# caphumidsens2_rev1_rc2.net
KiCad netlist of a schematic drawn in EAGLE
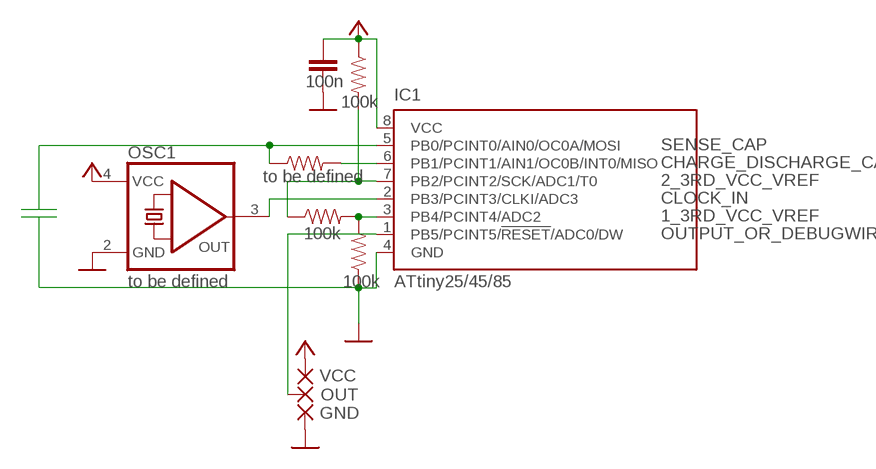
[diagram p0: schematic, sheet 1]

(export (version "E")
  (design (tool "Eeschema 10.0.6"))
  (components
    (comp (ref "C1")
      (value "100n")
      (footprint "eagle-import:0805")
      (libsource (lib "eagle-import") (part "CAP0805"))
    )
    (comp (ref "GND")
      (value "WIREPADSMD2,54-5,08")
      (footprint "eagle-import:SMD1,27-2,54")
      (libsource (lib "eagle-import") (part "SMD2"))
    )
    (comp (ref "IC1")
      (value "ATtiny25/45/85")
      (footprint "eagle-import:8S1")
      (fields (field (name "MPN") "ATTINY13V-10SSU"))
      (libsource (lib "eagle-import") (part "TINY13SSUV-10"))
    )
    (comp (ref "OSC1")
      (value "to be defined")
      (footprint "eagle-import:XO32")
      (libsource (lib "eagle-import") (part "XO32-OSCILLATOR"))
    )
    (comp (ref "OUT")
      (value "WIREPADSMD2,54-5,08")
      (footprint "eagle-import:SMD1,27-2,54")
      (libsource (lib "eagle-import") (part "SMD2"))
    )
    (comp (ref "R1")
      (value "100k")
      (footprint "eagle-import:0805")
      (libsource (lib "eagle-import") (part "RESISTOR0805-RES"))
    )
    (comp (ref "R2")
      (value "100k")
      (footprint "eagle-import:0805")
      (libsource (lib "eagle-import") (part "RESISTOR0805-RES"))
    )
    (comp (ref "R3")
      (value "100k")
      (footprint "eagle-import:0805")
      (libsource (lib "eagle-import") (part "RESISTOR0805-RES"))
    )
    (comp (ref "R4")
      (value "to be defined")
      (footprint "eagle-import:0805")
      (libsource (lib "eagle-import") (part "RESISTOR0805-RES"))
    )
    (comp (ref "VCC")
      (value "WIREPADSMD2,54-5,08")
      (footprint "eagle-import:SMD1,27-2,54")
      (libsource (lib "eagle-import") (part "SMD2"))
    )
  )
  (nets
    (net (code "1") (name "/1_3RD_VCC_VREF") (class "Default")
      (node (ref "IC1") (pin "3") (pinfunction "PB4/PCINT4/ADC2_3") (pintype "bidirectional"))
      (node (ref "R2") (pin "2") (pinfunction "2_2") (pintype "passive"))
      (node (ref "R3") (pin "2") (pinfunction "2_2") (pintype "passive"))
    )
    (net (code "2") (name "/2_3RD_VCC_VREF") (class "Default")
      (node (ref "IC1") (pin "7") (pinfunction "PB2/PCINT2/SCK/ADC1/T0_7") (pintype "bidirectional"))
      (node (ref "R1") (pin "2") (pinfunction "2_2") (pintype "passive"))
      (node (ref "R2") (pin "1") (pinfunction "1_1") (pintype "passive"))
    )
    (net (code "3") (name "/CHARGE_DISCHARGE_CAP") (class "Default")
      (node (ref "IC1") (pin "6") (pinfunction "PB1/PCINT1/AIN1/OC0B/INT0/MISO_6") (pintype "bidirectional"))
      (node (ref "R4") (pin "2") (pinfunction "2_2") (pintype "passive"))
    )
    (net (code "4") (name "/CLOCK_IN") (class "Default")
      (node (ref "IC1") (pin "2") (pinfunction "PB3/PCINT3/CLKI/ADC3_2") (pintype "bidirectional"))
      (node (ref "OSC1") (pin "3") (pinfunction "OUT_3") (pintype "output"))
    )
    (net (code "5") (name "/OUTPUT_OR_DEBUGWIRE") (class "Default")
      (node (ref "IC1") (pin "1") (pinfunction "PB5/PCINT5/~{RESET}/ADC0/DW_1") (pintype "bidirectional"))
      (node (ref "OUT") (pin "1") (pinfunction "P_1") (pintype "passive"))
    )
    (net (code "6") (name "/SENSE_CAP") (class "Default")
      (node (ref "IC1") (pin "5") (pinfunction "PB0/PCINT0/AIN0/OC0A/MOSI_5") (pintype "bidirectional"))
      (node (ref "R4") (pin "1") (pinfunction "1_1") (pintype "passive"))
    )
    (net (code "7") (name "GND") (class "Default")
      (node (ref "C1") (pin "1") (pinfunction "1_1") (pintype "passive"))
      (node (ref "GND") (pin "1") (pinfunction "P_1") (pintype "passive"))
      (node (ref "IC1") (pin "4") (pinfunction "GND_4") (pintype "power_in"))
      (node (ref "OSC1") (pin "2") (pinfunction "GND_2") (pintype "power_in"))
      (node (ref "R3") (pin "1") (pinfunction "1_1") (pintype "passive"))
    )
    (net (code "8") (name "VCC") (class "Default")
      (node (ref "C1") (pin "2") (pinfunction "2_2") (pintype "passive"))
      (node (ref "IC1") (pin "8") (pinfunction "VCC_8") (pintype "power_in"))
      (node (ref "OSC1") (pin "4") (pinfunction "VCC_4") (pintype "power_in"))
      (node (ref "R1") (pin "1") (pinfunction "1_1") (pintype "passive"))
      (node (ref "VCC") (pin "1") (pinfunction "P_1") (pintype "passive"))
    )
  )
)
